# satshakit-grbl.net
KiCad netlist of a schematic drawn in EAGLE
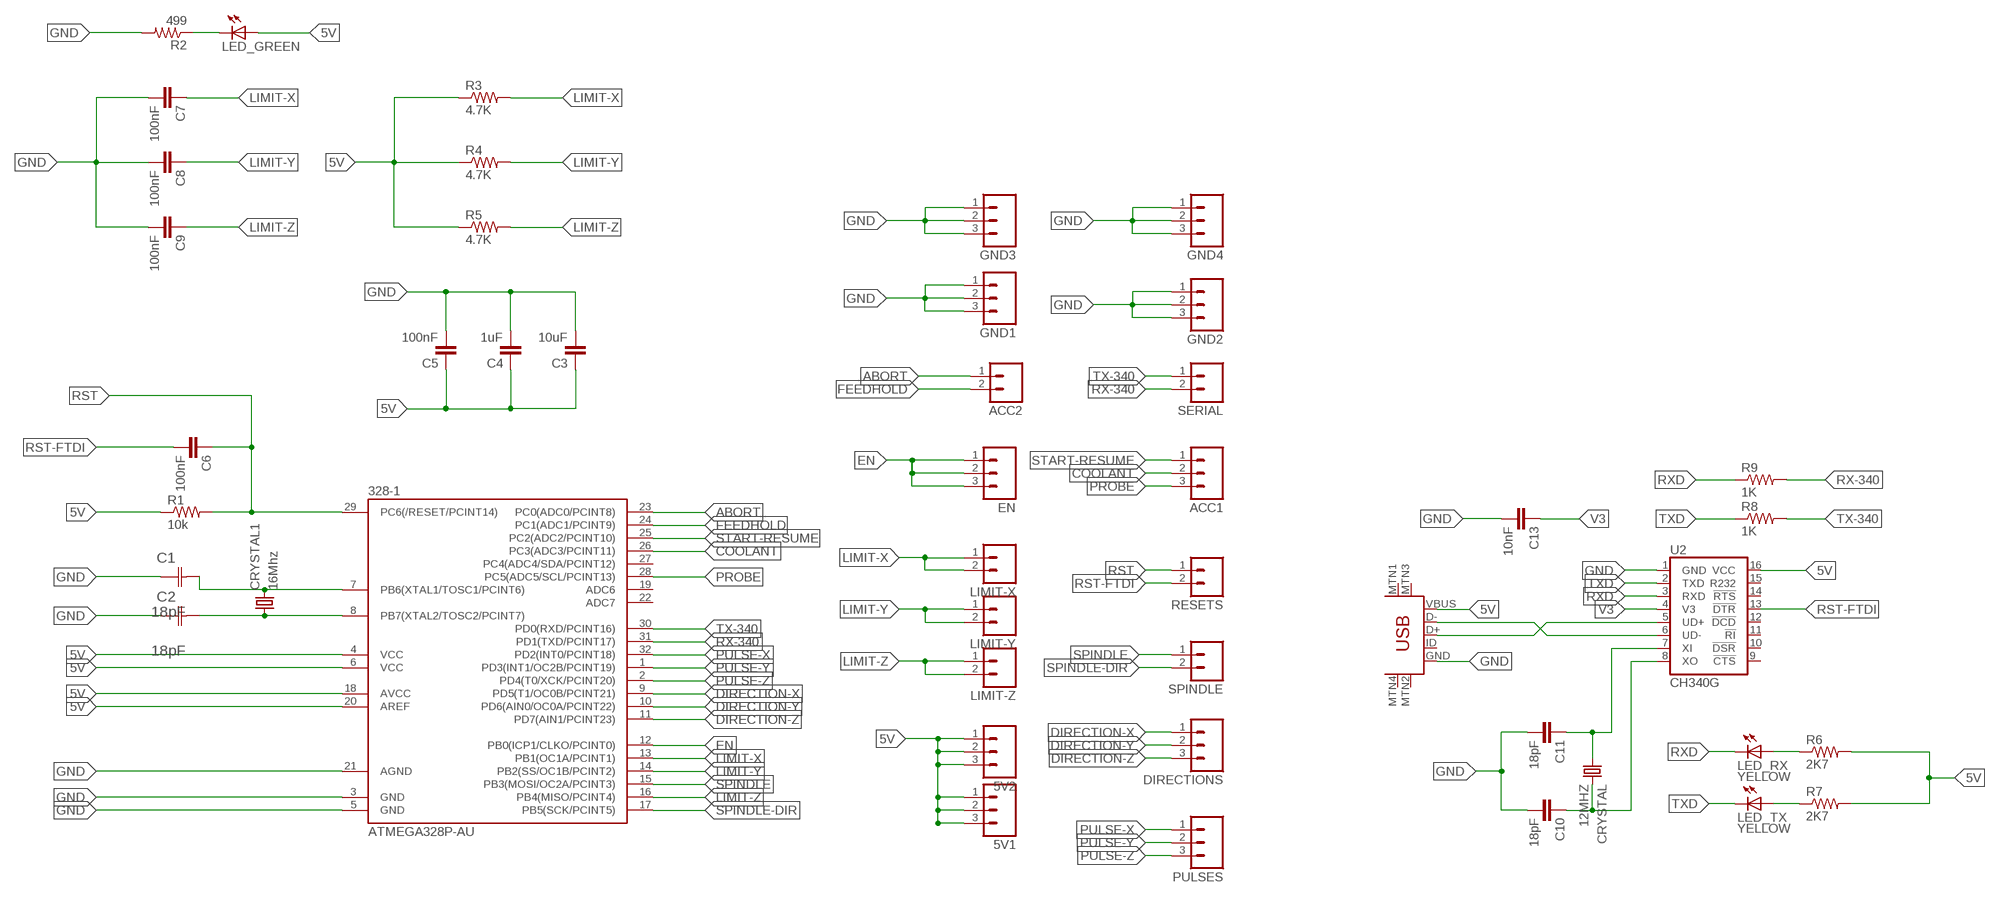
[diagram p0: schematic, sheet 1]

(export (version "E")
  (design (tool "Eeschema 10.0.6"))
  (components
    (comp (ref "5V1")
      (value "M03")
      (footprint "eagle-import:03P")
      (libsource (lib "eagle-import") (part "M03"))
    )
    (comp (ref "5V2")
      (value "M03")
      (footprint "eagle-import:03P")
      (libsource (lib "eagle-import") (part "M03"))
    )
    (comp (ref "328-1")
      (value "ATMEGA328P-AU")
      (footprint "eagle-import:TQFP32-08")
      (libsource (lib "eagle-import") (part "ATMEGA48/88/168-AU"))
    )
    (comp (ref "ACC1")
      (value "M03")
      (footprint "eagle-import:03P")
      (libsource (lib "eagle-import") (part "M03"))
    )
    (comp (ref "ACC2")
      (value "M02")
      (footprint "eagle-import:02P")
      (libsource (lib "eagle-import") (part "M02"))
    )
    (comp (ref "C1")
      (value "18pF")
      (footprint "eagle-import:CAPC3216X178N")
      (fields (field (name "MPN") "0612ZC225MAT2A") (field (name "TOLERANCE") "±20%"))
      (libsource (lib "eagle-import") (part "0612ZC225MAT2A"))
    )
    (comp (ref "C2")
      (value "18pF")
      (footprint "eagle-import:CAPC3216X178N")
      (fields (field (name "MPN") "0612ZC225MAT2A") (field (name "TOLERANCE") "±20%"))
      (libsource (lib "eagle-import") (part "0612ZC225MAT2A"))
    )
    (comp (ref "C3")
      (value "10uF")
      (footprint "eagle-import:1206")
      (libsource (lib "eagle-import") (part "CAP1206"))
    )
    (comp (ref "C4")
      (value "1uF")
      (footprint "eagle-import:1206")
      (libsource (lib "eagle-import") (part "CAP1206"))
    )
    (comp (ref "C5")
      (value "100nF")
      (footprint "eagle-import:1206")
      (libsource (lib "eagle-import") (part "CAP1206"))
    )
    (comp (ref "C6")
      (value "100nF")
      (footprint "eagle-import:1206")
      (libsource (lib "eagle-import") (part "CAP1206"))
    )
    (comp (ref "C7")
      (value "100nF")
      (footprint "eagle-import:1206")
      (libsource (lib "eagle-import") (part "CAP1206"))
    )
    (comp (ref "C8")
      (value "100nF")
      (footprint "eagle-import:1206")
      (libsource (lib "eagle-import") (part "CAP1206"))
    )
    (comp (ref "C9")
      (value "100nF")
      (footprint "eagle-import:1206")
      (libsource (lib "eagle-import") (part "CAP1206"))
    )
    (comp (ref "C10")
      (value "18pF")
      (footprint "eagle-import:1206")
      (libsource (lib "eagle-import") (part "CAP1206"))
    )
    (comp (ref "C11")
      (value "18pF")
      (footprint "eagle-import:1206")
      (libsource (lib "eagle-import") (part "CAP1206"))
    )
    (comp (ref "C13")
      (value "10nF")
      (footprint "eagle-import:1206")
      (libsource (lib "eagle-import") (part "CAP1206"))
    )
    (comp (ref "CRYSTAL")
      (value "12MHZ")
      (footprint "eagle-import:CSM-7X-DU")
      (libsource (lib "eagle-import") (part "flight_controller.lbr01_FAB_Hello_CSM-7X-DU"))
    )
    (comp (ref "CRYSTAL1")
      (value "16Mhz")
      (footprint "eagle-import:CSM-7X-DU")
      (libsource (lib "eagle-import") (part "CSM-7X-DU"))
    )
    (comp (ref "DIRECTIONS")
      (value "M03")
      (footprint "eagle-import:03P")
      (libsource (lib "eagle-import") (part "M03"))
    )
    (comp (ref "EN")
      (value "M03")
      (footprint "eagle-import:03P")
      (libsource (lib "eagle-import") (part "M03"))
    )
    (comp (ref "GND1")
      (value "M03")
      (footprint "eagle-import:03P")
      (libsource (lib "eagle-import") (part "M03"))
    )
    (comp (ref "GND2")
      (value "M03")
      (footprint "eagle-import:03P")
      (libsource (lib "eagle-import") (part "M03"))
    )
    (comp (ref "GND3")
      (value "M03")
      (footprint "eagle-import:03P")
      (libsource (lib "eagle-import") (part "M03"))
    )
    (comp (ref "GND4")
      (value "M03")
      (footprint "eagle-import:03P")
      (libsource (lib "eagle-import") (part "M03"))
    )
    (comp (ref "LED_GREEN")
      (value "LED1206")
      (footprint "eagle-import:1206")
      (libsource (lib "eagle-import") (part "LED1206"))
    )
    (comp (ref "LED_RX")
      (value "YELLOW")
      (footprint "eagle-import:LED1206")
      (libsource (lib "eagle-import") (part "LED"))
    )
    (comp (ref "LED_TX")
      (value "YELLOW")
      (footprint "eagle-import:LED1206")
      (libsource (lib "eagle-import") (part "LED"))
    )
    (comp (ref "LIMIT-X")
      (value "M02")
      (footprint "eagle-import:02P")
      (libsource (lib "eagle-import") (part "M02"))
    )
    (comp (ref "LIMIT-Y")
      (value "M02")
      (footprint "eagle-import:02P")
      (libsource (lib "eagle-import") (part "M02"))
    )
    (comp (ref "LIMIT-Z")
      (value "M02")
      (footprint "eagle-import:02P")
      (libsource (lib "eagle-import") (part "M02"))
    )
    (comp (ref "PULSES")
      (value "M03")
      (footprint "eagle-import:03P")
      (libsource (lib "eagle-import") (part "M03"))
    )
    (comp (ref "R1")
      (value "10k")
      (footprint "eagle-import:1206")
      (libsource (lib "eagle-import") (part "RESISTOR1206"))
    )
    (comp (ref "R2")
      (value "499")
      (footprint "eagle-import:1206")
      (libsource (lib "eagle-import") (part "RESISTOR1206"))
    )
    (comp (ref "R3")
      (value "4.7K")
      (footprint "eagle-import:1206")
      (libsource (lib "eagle-import") (part "RESISTOR1206"))
    )
    (comp (ref "R4")
      (value "4.7K")
      (footprint "eagle-import:1206")
      (libsource (lib "eagle-import") (part "RESISTOR1206"))
    )
    (comp (ref "R5")
      (value "4.7K")
      (footprint "eagle-import:1206")
      (libsource (lib "eagle-import") (part "RESISTOR1206"))
    )
    (comp (ref "R6")
      (value "2K7")
      (footprint "eagle-import:R1206")
      (libsource (lib "eagle-import") (part "RES-US1206"))
    )
    (comp (ref "R7")
      (value "2K7")
      (footprint "eagle-import:R1206")
      (libsource (lib "eagle-import") (part "RES-US1206"))
    )
    (comp (ref "R8")
      (value "1K")
      (footprint "eagle-import:R1206")
      (libsource (lib "eagle-import") (part "RES-US1206"))
    )
    (comp (ref "R9")
      (value "1K")
      (footprint "eagle-import:R1206")
      (libsource (lib "eagle-import") (part "RES-US1206"))
    )
    (comp (ref "RESETS")
      (value "M02")
      (footprint "eagle-import:02P")
      (libsource (lib "eagle-import") (part "M02"))
    )
    (comp (ref "SERIAL")
      (value "M02")
      (footprint "eagle-import:02P")
      (libsource (lib "eagle-import") (part "M02"))
    )
    (comp (ref "SPINDLE")
      (value "M02")
      (footprint "eagle-import:02P")
      (libsource (lib "eagle-import") (part "M02"))
    )
    (comp (ref "U$7")
      (value "USB-MINIB-5PIN")
      (footprint "eagle-import:USB-MINIB")
      (libsource (lib "eagle-import") (part "USB-MINIB-5PIN"))
    )
    (comp (ref "U2")
      (value "CH340G")
      (footprint "eagle-import:SO016")
      (libsource (lib "eagle-import") (part "CH340GSMD"))
    )
  )
  (nets
    (net (code "1") (name "5V") (class "Default")
      (node (ref "328-1") (pin "18") (pinfunction "AVCC_18") (pintype "passive"))
      (node (ref "328-1") (pin "20") (pinfunction "AREF_20") (pintype "passive"))
      (node (ref "328-1") (pin "4") (pinfunction "VCC_4") (pintype "power_in"))
      (node (ref "328-1") (pin "6") (pinfunction "VCC_6") (pintype "power_in"))
      (node (ref "5V1") (pin "1") (pinfunction "1_1") (pintype "passive"))
      (node (ref "5V1") (pin "2") (pinfunction "2_2") (pintype "passive"))
      (node (ref "5V1") (pin "3") (pinfunction "3_3") (pintype "passive"))
      (node (ref "5V2") (pin "1") (pinfunction "1_1") (pintype "passive"))
      (node (ref "5V2") (pin "2") (pinfunction "2_2") (pintype "passive"))
      (node (ref "5V2") (pin "3") (pinfunction "3_3") (pintype "passive"))
      (node (ref "C3") (pin "1") (pinfunction "1_1") (pintype "passive"))
      (node (ref "C4") (pin "1") (pinfunction "1_1") (pintype "passive"))
      (node (ref "C5") (pin "1") (pinfunction "1_1") (pintype "passive"))
      (node (ref "LED_GREEN") (pin "1") (pinfunction "A_1") (pintype "passive"))
      (node (ref "R1") (pin "1") (pinfunction "1_1") (pintype "passive"))
      (node (ref "R3") (pin "1") (pinfunction "1_1") (pintype "passive"))
      (node (ref "R4") (pin "1") (pinfunction "1_1") (pintype "passive"))
      (node (ref "R5") (pin "1") (pinfunction "1_1") (pintype "passive"))
      (node (ref "R6") (pin "2") (pinfunction "2_2") (pintype "passive"))
      (node (ref "R7") (pin "2") (pinfunction "2_2") (pintype "passive"))
      (node (ref "U$7") (pin "VBUS") (pinfunction "VBUS_VBUS") (pintype "bidirectional"))
      (node (ref "U2") (pin "16") (pinfunction "VCC_16") (pintype "bidirectional"))
    )
    (net (code "2") (name "ABORT") (class "Default")
      (node (ref "328-1") (pin "23") (pinfunction "PC0(ADC0/PCINT8)_23") (pintype "bidirectional"))
      (node (ref "ACC2") (pin "1") (pinfunction "1_1") (pintype "passive"))
    )
    (net (code "3") (name "COOLANT") (class "Default")
      (node (ref "328-1") (pin "26") (pinfunction "PC3(ADC3/PCINT11)_26") (pintype "bidirectional"))
      (node (ref "ACC1") (pin "2") (pinfunction "2_2") (pintype "passive"))
    )
    (net (code "4") (name "DIRECTION-X") (class "Default")
      (node (ref "328-1") (pin "9") (pinfunction "PD5(T1/OC0B/PCINT21)_9") (pintype "bidirectional"))
      (node (ref "DIRECTIONS") (pin "1") (pinfunction "1_1") (pintype "passive"))
    )
    (net (code "5") (name "DIRECTION-Y") (class "Default")
      (node (ref "328-1") (pin "10") (pinfunction "PD6(AIN0/OC0A/PCINT22)_10") (pintype "bidirectional"))
      (node (ref "DIRECTIONS") (pin "2") (pinfunction "2_2") (pintype "passive"))
    )
    (net (code "6") (name "DIRECTION-Z") (class "Default")
      (node (ref "328-1") (pin "11") (pinfunction "PD7(AIN1/PCINT23)_11") (pintype "bidirectional"))
      (node (ref "DIRECTIONS") (pin "3") (pinfunction "3_3") (pintype "passive"))
    )
    (net (code "7") (name "EN") (class "Default")
      (node (ref "328-1") (pin "12") (pinfunction "PB0(ICP1/CLKO/PCINT0)_12") (pintype "bidirectional"))
      (node (ref "EN") (pin "1") (pinfunction "1_1") (pintype "passive"))
      (node (ref "EN") (pin "2") (pinfunction "2_2") (pintype "passive"))
      (node (ref "EN") (pin "3") (pinfunction "3_3") (pintype "passive"))
    )
    (net (code "8") (name "FEEDHOLD") (class "Default")
      (node (ref "328-1") (pin "24") (pinfunction "PC1(ADC1/PCINT9)_24") (pintype "bidirectional"))
      (node (ref "ACC2") (pin "2") (pinfunction "2_2") (pintype "passive"))
    )
    (net (code "9") (name "GND") (class "Default")
      (node (ref "328-1") (pin "21") (pinfunction "AGND_21") (pintype "power_in"))
      (node (ref "328-1") (pin "3") (pinfunction "GND_3") (pintype "power_in"))
      (node (ref "328-1") (pin "5") (pinfunction "GND_5") (pintype "power_in"))
      (node (ref "C1") (pin "1") (pinfunction "C1_1") (pintype "passive"))
      (node (ref "C10") (pin "2") (pinfunction "2_2") (pintype "passive"))
      (node (ref "C11") (pin "2") (pinfunction "2_2") (pintype "passive"))
      (node (ref "C13") (pin "2") (pinfunction "2_2") (pintype "passive"))
      (node (ref "C2") (pin "1") (pinfunction "C1_1") (pintype "passive"))
      (node (ref "C3") (pin "2") (pinfunction "2_2") (pintype "passive"))
      (node (ref "C4") (pin "2") (pinfunction "2_2") (pintype "passive"))
      (node (ref "C5") (pin "2") (pinfunction "2_2") (pintype "passive"))
      (node (ref "C7") (pin "2") (pinfunction "2_2") (pintype "passive"))
      (node (ref "C8") (pin "2") (pinfunction "2_2") (pintype "passive"))
      (node (ref "C9") (pin "2") (pinfunction "2_2") (pintype "passive"))
      (node (ref "GND1") (pin "1") (pinfunction "1_1") (pintype "passive"))
      (node (ref "GND1") (pin "2") (pinfunction "2_2") (pintype "passive"))
      (node (ref "GND1") (pin "3") (pinfunction "3_3") (pintype "passive"))
      (node (ref "GND2") (pin "1") (pinfunction "1_1") (pintype "passive"))
      (node (ref "GND2") (pin "2") (pinfunction "2_2") (pintype "passive"))
      (node (ref "GND2") (pin "3") (pinfunction "3_3") (pintype "passive"))
      (node (ref "GND3") (pin "1") (pinfunction "1_1") (pintype "passive"))
      (node (ref "GND3") (pin "2") (pinfunction "2_2") (pintype "passive"))
      (node (ref "GND3") (pin "3") (pinfunction "3_3") (pintype "passive"))
      (node (ref "GND4") (pin "1") (pinfunction "1_1") (pintype "passive"))
      (node (ref "GND4") (pin "2") (pinfunction "2_2") (pintype "passive"))
      (node (ref "GND4") (pin "3") (pinfunction "3_3") (pintype "passive"))
      (node (ref "R2") (pin "2") (pinfunction "2_2") (pintype "passive"))
      (node (ref "U$7") (pin "GND") (pinfunction "GND_GND") (pintype "bidirectional"))
      (node (ref "U2") (pin "1") (pinfunction "GND_1") (pintype "bidirectional"))
    )
    (net (code "10") (name "LIMIT-X") (class "Default")
      (node (ref "328-1") (pin "13") (pinfunction "PB1(OC1A/PCINT1)_13") (pintype "bidirectional"))
      (node (ref "C7") (pin "1") (pinfunction "1_1") (pintype "passive"))
      (node (ref "LIMIT-X") (pin "1") (pinfunction "1_1") (pintype "passive"))
      (node (ref "LIMIT-X") (pin "2") (pinfunction "2_2") (pintype "passive"))
      (node (ref "R3") (pin "2") (pinfunction "2_2") (pintype "passive"))
    )
    (net (code "11") (name "LIMIT-Y") (class "Default")
      (node (ref "328-1") (pin "14") (pinfunction "PB2(SS/OC1B/PCINT2)_14") (pintype "bidirectional"))
      (node (ref "C8") (pin "1") (pinfunction "1_1") (pintype "passive"))
      (node (ref "LIMIT-Y") (pin "1") (pinfunction "1_1") (pintype "passive"))
      (node (ref "LIMIT-Y") (pin "2") (pinfunction "2_2") (pintype "passive"))
      (node (ref "R4") (pin "2") (pinfunction "2_2") (pintype "passive"))
    )
    (net (code "12") (name "LIMIT-Z") (class "Default")
      (node (ref "328-1") (pin "16") (pinfunction "PB4(MISO/PCINT4)_16") (pintype "bidirectional"))
      (node (ref "C9") (pin "1") (pinfunction "1_1") (pintype "passive"))
      (node (ref "LIMIT-Z") (pin "1") (pinfunction "1_1") (pintype "passive"))
      (node (ref "LIMIT-Z") (pin "2") (pinfunction "2_2") (pintype "passive"))
      (node (ref "R5") (pin "2") (pinfunction "2_2") (pintype "passive"))
    )
    (net (code "13") (name "Net-(328-1-PB6(XTAL1{slash}TOSC1{slash}PCINT6))") (class "Default")
      (node (ref "328-1") (pin "7") (pinfunction "PB6(XTAL1/TOSC1/PCINT6)_7") (pintype "bidirectional"))
      (node (ref "C1") (pin "2") (pinfunction "C2_2") (pintype "passive"))
      (node (ref "CRYSTAL1") (pin "2") (pinfunction "2_2") (pintype "passive"))
    )
    (net (code "14") (name "Net-(328-1-PB7(XTAL2{slash}TOSC2{slash}PCINT7))") (class "Default")
      (node (ref "328-1") (pin "8") (pinfunction "PB7(XTAL2/TOSC2/PCINT7)_8") (pintype "bidirectional"))
      (node (ref "C2") (pin "2") (pinfunction "C2_2") (pintype "passive"))
      (node (ref "CRYSTAL1") (pin "1") (pinfunction "1_1") (pintype "passive"))
    )
    (net (code "15") (name "Net-(LED_GREEN-C)") (class "Default")
      (node (ref "LED_GREEN") (pin "2") (pinfunction "C_2") (pintype "passive"))
      (node (ref "R2") (pin "1") (pinfunction "1_1") (pintype "passive"))
    )
    (net (code "16") (name "Net-(LED_RX-A)") (class "Default")
      (node (ref "LED_RX") (pin "1") (pinfunction "A_1") (pintype "passive"))
      (node (ref "R6") (pin "1") (pinfunction "1_1") (pintype "passive"))
    )
    (net (code "17") (name "Net-(LED_TX-A)") (class "Default")
      (node (ref "LED_TX") (pin "1") (pinfunction "A_1") (pintype "passive"))
      (node (ref "R7") (pin "1") (pinfunction "1_1") (pintype "passive"))
    )
    (net (code "18") (name "Net-(U2-UD+)") (class "Default")
      (node (ref "U$7") (pin "D+") (pinfunction "D+_D+") (pintype "bidirectional"))
      (node (ref "U2") (pin "5") (pinfunction "UD+_5") (pintype "bidirectional"))
    )
    (net (code "19") (name "Net-(U2-UD-)") (class "Default")
      (node (ref "U$7") (pin "D-") (pinfunction "D-_D-") (pintype "bidirectional"))
      (node (ref "U2") (pin "6") (pinfunction "UD-_6") (pintype "bidirectional"))
    )
    (net (code "20") (name "Net-(U2-XI)") (class "Default")
      (node (ref "C11") (pin "1") (pinfunction "1_1") (pintype "passive"))
      (node (ref "CRYSTAL") (pin "1") (pinfunction "1_1") (pintype "passive"))
      (node (ref "U2") (pin "7") (pinfunction "XI_7") (pintype "bidirectional"))
    )
    (net (code "21") (name "Net-(U2-XO)") (class "Default")
      (node (ref "C10") (pin "1") (pinfunction "1_1") (pintype "passive"))
      (node (ref "CRYSTAL") (pin "2") (pinfunction "2_2") (pintype "passive"))
      (node (ref "U2") (pin "8") (pinfunction "XO_8") (pintype "bidirectional"))
    )
    (net (code "22") (name "PROBE") (class "Default")
      (node (ref "328-1") (pin "28") (pinfunction "PC5(ADC5/SCL/PCINT13)_28") (pintype "bidirectional"))
      (node (ref "ACC1") (pin "3") (pinfunction "3_3") (pintype "passive"))
    )
    (net (code "23") (name "PULSE-X") (class "Default")
      (node (ref "328-1") (pin "32") (pinfunction "PD2(INT0/PCINT18)_32") (pintype "bidirectional"))
      (node (ref "PULSES") (pin "1") (pinfunction "1_1") (pintype "passive"))
    )
    (net (code "24") (name "PULSE-Y") (class "Default")
      (node (ref "328-1") (pin "1") (pinfunction "PD3(INT1/OC2B/PCINT19)_1") (pintype "bidirectional"))
      (node (ref "PULSES") (pin "2") (pinfunction "2_2") (pintype "passive"))
    )
    (net (code "25") (name "PULSE-Z") (class "Default")
      (node (ref "328-1") (pin "2") (pinfunction "PD4(T0/XCK/PCINT20)_2") (pintype "bidirectional"))
      (node (ref "PULSES") (pin "3") (pinfunction "3_3") (pintype "passive"))
    )
    (net (code "26") (name "RST") (class "Default")
      (node (ref "328-1") (pin "29") (pinfunction "PC6(/RESET/PCINT14)_29") (pintype "bidirectional"))
      (node (ref "C6") (pin "1") (pinfunction "1_1") (pintype "passive"))
      (node (ref "R1") (pin "2") (pinfunction "2_2") (pintype "passive"))
      (node (ref "RESETS") (pin "1") (pinfunction "1_1") (pintype "passive"))
    )
    (net (code "27") (name "RST-FTDI") (class "Default")
      (node (ref "C6") (pin "2") (pinfunction "2_2") (pintype "passive"))
      (node (ref "RESETS") (pin "2") (pinfunction "2_2") (pintype "passive"))
      (node (ref "U2") (pin "13") (pinfunction "~{DTR}_13") (pintype "bidirectional"))
    )
    (net (code "28") (name "RX-340") (class "Default")
      (node (ref "328-1") (pin "31") (pinfunction "PD1(TXD/PCINT17)_31") (pintype "bidirectional"))
      (node (ref "R9") (pin "2") (pinfunction "2_2") (pintype "passive"))
      (node (ref "SERIAL") (pin "2") (pinfunction "2_2") (pintype "passive"))
    )
    (net (code "29") (name "RXD") (class "Default")
      (node (ref "LED_RX") (pin "2") (pinfunction "C_2") (pintype "passive"))
      (node (ref "R9") (pin "1") (pinfunction "1_1") (pintype "passive"))
      (node (ref "U2") (pin "3") (pinfunction "RXD_3") (pintype "bidirectional"))
    )
    (net (code "30") (name "SPINDLE") (class "Default")
      (node (ref "328-1") (pin "15") (pinfunction "PB3(MOSI/OC2A/PCINT3)_15") (pintype "bidirectional"))
      (node (ref "SPINDLE") (pin "1") (pinfunction "1_1") (pintype "passive"))
    )
    (net (code "31") (name "SPINDLE-DIR") (class "Default")
      (node (ref "328-1") (pin "17") (pinfunction "PB5(SCK/PCINT5)_17") (pintype "bidirectional"))
      (node (ref "SPINDLE") (pin "2") (pinfunction "2_2") (pintype "passive"))
    )
    (net (code "32") (name "START-RESUME") (class "Default")
      (node (ref "328-1") (pin "25") (pinfunction "PC2(ADC2/PCINT10)_25") (pintype "bidirectional"))
      (node (ref "ACC1") (pin "1") (pinfunction "1_1") (pintype "passive"))
    )
    (net (code "33") (name "TX-340") (class "Default")
      (node (ref "328-1") (pin "30") (pinfunction "PD0(RXD/PCINT16)_30") (pintype "bidirectional"))
      (node (ref "R8") (pin "2") (pinfunction "2_2") (pintype "passive"))
      (node (ref "SERIAL") (pin "1") (pinfunction "1_1") (pintype "passive"))
    )
    (net (code "34") (name "TXD") (class "Default")
      (node (ref "LED_TX") (pin "2") (pinfunction "C_2") (pintype "passive"))
      (node (ref "R8") (pin "1") (pinfunction "1_1") (pintype "passive"))
      (node (ref "U2") (pin "2") (pinfunction "TXD_2") (pintype "bidirectional"))
    )
    (net (code "35") (name "V3") (class "Default")
      (node (ref "C13") (pin "1") (pinfunction "1_1") (pintype "passive"))
      (node (ref "U2") (pin "4") (pinfunction "V3_4") (pintype "bidirectional"))
    )
    (net (code "36") (name "unconnected-(328-1-ADC6-Pad19)") (class "Default")
      (node (ref "328-1") (pin "19") (pinfunction "ADC6_19") (pintype "passive"))
    )
    (net (code "37") (name "unconnected-(328-1-ADC7-Pad22)") (class "Default")
      (node (ref "328-1") (pin "22") (pinfunction "ADC7_22") (pintype "passive"))
    )
    (net (code "38") (name "unconnected-(328-1-PC4(ADC4{slash}SDA{slash}PCINT12)-Pad27)") (class "Default")
      (node (ref "328-1") (pin "27") (pinfunction "PC4(ADC4/SDA/PCINT12)_27") (pintype "bidirectional"))
    )
    (net (code "39") (name "unconnected-(U$7-MTN1-PadMTN3)") (class "Default")
      (node (ref "U$7") (pin "MTN3") (pinfunction "MTN1_MTN3") (pintype "bidirectional"))
    )
    (net (code "40") (name "unconnected-(U$7-MTN2-PadMTN1)") (class "Default")
      (node (ref "U$7") (pin "MTN1") (pinfunction "MTN2_MTN1") (pintype "bidirectional"))
    )
    (net (code "41") (name "unconnected-(U$7-MTN3-PadMTN2)") (class "Default")
      (node (ref "U$7") (pin "MTN2") (pinfunction "MTN3_MTN2") (pintype "bidirectional"))
    )
    (net (code "42") (name "unconnected-(U$7-PadID)") (class "Default")
      (node (ref "U$7") (pin "ID") (pinfunction "ID_ID") (pintype "bidirectional"))
    )
    (net (code "43") (name "unconnected-(U$7-PadMTN4)") (class "Default")
      (node (ref "U$7") (pin "MTN4") (pinfunction "MTN4_MTN4") (pintype "bidirectional"))
    )
    (net (code "44") (name "unconnected-(U2-R232-Pad15)") (class "Default")
      (node (ref "U2") (pin "15") (pinfunction "R232_15") (pintype "bidirectional"))
    )
    (net (code "45") (name "unconnected-(U2-~{CTS}-Pad9)") (class "Default")
      (node (ref "U2") (pin "9") (pinfunction "~{CTS}_9") (pintype "bidirectional"))
    )
    (net (code "46") (name "unconnected-(U2-~{DCD}-Pad12)") (class "Default")
      (node (ref "U2") (pin "12") (pinfunction "~{DCD}_12") (pintype "bidirectional"))
    )
    (net (code "47") (name "unconnected-(U2-~{DSR}-Pad10)") (class "Default")
      (node (ref "U2") (pin "10") (pinfunction "~{DSR}_10") (pintype "bidirectional"))
    )
    (net (code "48") (name "unconnected-(U2-~{RI}-Pad11)") (class "Default")
      (node (ref "U2") (pin "11") (pinfunction "~{RI}_11") (pintype "bidirectional"))
    )
    (net (code "49") (name "unconnected-(U2-~{RTS}-Pad14)") (class "Default")
      (node (ref "U2") (pin "14") (pinfunction "~{RTS}_14") (pintype "bidirectional"))
    )
  )
)
